# 02_PSU.net
KiCad netlist of a schematic drawn in Altium Designer
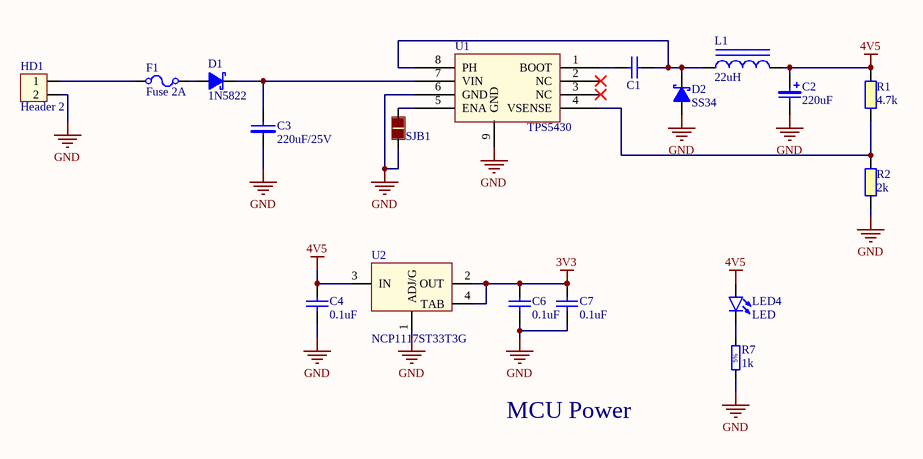
[diagram p0: [02].PSU.SchDoc]

(export (version "E")
  (design (tool "Eeschema 10.0.6"))
  (components
    (comp (ref "C1") (value "0.01uF") (footprint "C_0603") (libsource (lib "DungMV") (part "CAP_0603")))
    (comp (ref "C2") (value "220uF") (footprint "Tantalum") (libsource (lib "Node_LoRA") (part "CAP_TANTA")))
    (comp (ref "C3")
      (value "220uF/25V")
      (footprint "CAP-ALU-SMD-6.3x7.7x2.2")
      (description "PANASONIC EEU-TP1E221B CAPACITOR ALUM ELEC, 220UF, 25V, 20%, RADIAL (1 piece)")
      (libsource (lib "Library") (part "Cap 220uF/25V"))
    )
    (comp (ref "C4") (value "0.1uF") (footprint "C_0603") (libsource (lib "DungMV") (part "CAP_0805")))
    (comp (ref "C6") (value "0.1uF") (footprint "C_0603") (libsource (lib "DungMV") (part "CAP_0805")))
    (comp (ref "C7") (value "0.1uF") (footprint "C_0603") (libsource (lib "DungMV") (part "CAP_0805")))
    (comp (ref "D1")
      (value "1N5822")
      (footprint "SS34")
      (description "3A 40V SS34")
      (libsource (lib "ThanhNT") (part "DIODE_1N5822"))
    )
    (comp (ref "D2")
      (value "SS34")
      (footprint "SS34")
      (description "DIODE SCHOTTKY 40V 3A SMC")
      (fields (field (name "MANUFACTURER") "ON Semiconductor / Fairchild") (field (name "VOLTAGE") "40V"))
      (libsource (lib "Node_LoRA") (part "SS34"))
    )
    (comp (ref "F1")
      (value "Fuse 2A")
      (footprint "FUSE_1812_4530")
      (libsource (lib "ThanhNT") (part "FUSE_SMD"))
    )
    (comp (ref "HD1")
      (value "Header 2")
      (footprint "HED2")
      (description "Header 2 (Green)")
      (libsource (lib "syhaunguyen") (part "Hed2"))
    )
    (comp (ref "L1") (value "22uH") (footprint "INDUCTOR") (libsource (lib "DungMV") (part "INDUCTOR")))
    (comp (ref "LED4") (value "LED") (footprint "LED_0805") (libsource (lib "ThanhNT") (part "LED_0805")))
    (comp (ref "R1") (value "4.7k") (footprint "R_0603") (libsource (lib "DungMV") (part "RES_0603")))
    (comp (ref "R2") (value "2k") (footprint "R_0603") (libsource (lib "DungMV") (part "RES_0603")))
    (comp (ref "R7")
      (value "1k")
      (footprint "R_0603")
      (description "Resistor - 5%")
      (fields
        (field (name "PART NUMBER") "RC0805JR-071KL")
        (field (name "POWER") "125 mW (1/8 W)")
        (field (name "AUTHOR") "MDBK")
      )
      (libsource (lib "Resistors") (part "Resistor - 5%"))
    )
    (comp (ref "SJB1")
      (value "SJB_SMD_2_0603")
      (footprint "SJB")
      (libsource (lib "DungMV") (part "SJB_SMD_2_0603"))
    )
    (comp (ref "U1") (value "TPS5430") (footprint "TPS5430") (libsource (lib "DungMV") (part "TPS5430")))
    (comp (ref "U2")
      (value "NCP1117ST33T3G")
      (footprint "AMS1117")
      (description "IC REG LINEAR 3.3V 1A SOT223")
      (libsource (lib "Node_LoRA") (part "NCP1117ST33T3G"))
    )
  )
  (nets
    (net (code "1") (name "3V3") (class "Default")
      (node (ref "C6") (pin "2") (pinfunction "2_2") (pintype "passive"))
      (node (ref "C7") (pin "2") (pinfunction "2_2") (pintype "passive"))
      (node (ref "U2") (pin "2") (pinfunction "OUT_2") (pintype "passive"))
      (node (ref "U2") (pin "4") (pinfunction "TAB_4") (pintype "passive"))
    )
    (net (code "2") (name "4V5") (class "Default")
      (node (ref "C2") (pin "A") (pinfunction "A_A") (pintype "passive"))
      (node (ref "C4") (pin "2") (pinfunction "2_2") (pintype "passive"))
      (node (ref "L1") (pin "2") (pinfunction "2_2") (pintype "passive"))
      (node (ref "LED4") (pin "A") (pinfunction "A_A") (pintype "passive"))
      (node (ref "R1") (pin "2") (pinfunction "2_2") (pintype "passive"))
      (node (ref "U2") (pin "3") (pinfunction "IN_3") (pintype "passive"))
    )
    (net (code "3") (name "GND") (class "Default")
      (node (ref "C2") (pin "K") (pinfunction "K_K") (pintype "passive"))
      (node (ref "C3") (pin "1") (pinfunction "1_1") (pintype "passive"))
      (node (ref "C4") (pin "1") (pinfunction "1_1") (pintype "passive"))
      (node (ref "C6") (pin "1") (pinfunction "1_1") (pintype "passive"))
      (node (ref "C7") (pin "1") (pinfunction "1_1") (pintype "passive"))
      (node (ref "D2") (pin "A") (pinfunction "A_A") (pintype "passive"))
      (node (ref "HD1") (pin "2") (pinfunction "2_2") (pintype "passive"))
      (node (ref "R2") (pin "1") (pinfunction "1_1") (pintype "passive"))
      (node (ref "R7") (pin "1") (pinfunction "1_1") (pintype "passive"))
      (node (ref "SJB1") (pin "1") (pintype "passive"))
      (node (ref "U1") (pin "6") (pinfunction "GND_6") (pintype "passive"))
      (node (ref "U1") (pin "9") (pinfunction "GND_9") (pintype "passive"))
      (node (ref "U2") (pin "1") (pinfunction "ADJ/G_1") (pintype "passive"))
    )
    (net (code "4") (name "Net-(D1-PadA)") (class "Default")
      (node (ref "D1") (pin "A") (pinfunction "A_A") (pintype "passive"))
      (node (ref "F1") (pin "2") (pinfunction "2_2") (pintype "passive"))
    )
    (net (code "5") (name "Net-(F1-Pad1)") (class "Default")
      (node (ref "F1") (pin "1") (pinfunction "1_1") (pintype "passive"))
      (node (ref "HD1") (pin "1") (pinfunction "1_1") (pintype "passive"))
    )
    (net (code "6") (name "Net-(LED4-PadK)") (class "Default")
      (node (ref "LED4") (pin "K") (pinfunction "K_K") (pintype "passive"))
      (node (ref "R7") (pin "2") (pinfunction "2_2") (pintype "passive"))
    )
    (net (code "7") (name "Net-(U1-BOOT)") (class "Default")
      (node (ref "C1") (pin "1") (pinfunction "1_1") (pintype "passive"))
      (node (ref "U1") (pin "1") (pinfunction "BOOT_1") (pintype "passive"))
    )
    (net (code "8") (name "Net-(U1-ENA)") (class "Default")
      (node (ref "SJB1") (pin "2") (pintype "passive"))
      (node (ref "U1") (pin "5") (pinfunction "ENA_5") (pintype "passive"))
    )
    (net (code "9") (name "Net-(U1-PH)") (class "Default")
      (node (ref "C1") (pin "2") (pinfunction "2_2") (pintype "passive"))
      (node (ref "D2") (pin "K") (pinfunction "K_K") (pintype "passive"))
      (node (ref "L1") (pin "1") (pinfunction "1_1") (pintype "passive"))
      (node (ref "U1") (pin "8") (pinfunction "PH_8") (pintype "passive"))
    )
    (net (code "10") (name "Net-(U1-VIN)") (class "Default")
      (node (ref "C3") (pin "2") (pinfunction "2_2") (pintype "passive"))
      (node (ref "D1") (pin "K") (pinfunction "K_K") (pintype "passive"))
      (node (ref "U1") (pin "7") (pinfunction "VIN_7") (pintype "passive"))
    )
    (net (code "11") (name "Net-(U1-VSENSE)") (class "Default")
      (node (ref "R1") (pin "1") (pinfunction "1_1") (pintype "passive"))
      (node (ref "R2") (pin "2") (pinfunction "2_2") (pintype "passive"))
      (node (ref "U1") (pin "4") (pinfunction "VSENSE_4") (pintype "passive"))
    )
    (net (code "12") (name "unconnected-(U1-NC-Pad2)") (class "Default")
      (node (ref "U1") (pin "2") (pinfunction "NC_2") (pintype "passive+no_connect"))
    )
    (net (code "13") (name "unconnected-(U1-NC-Pad3)") (class "Default")
      (node (ref "U1") (pin "3") (pinfunction "NC_3") (pintype "passive+no_connect"))
    )
  )
)
